# platform_smd2_driver.net
KiCad netlist of a schematic drawn in EAGLE
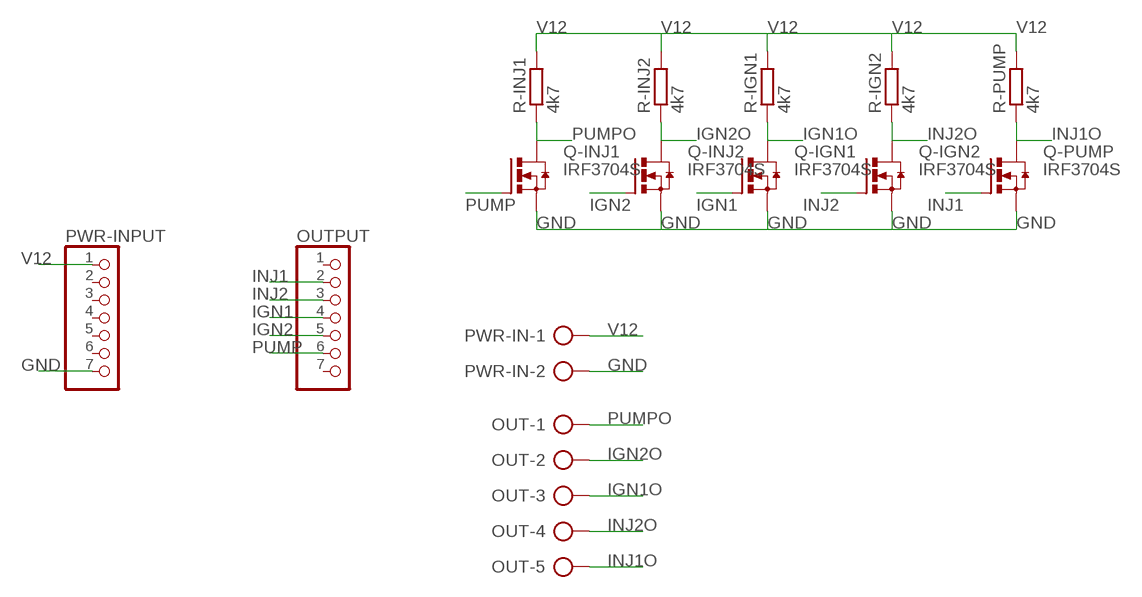
[diagram p0: schematic, sheet 1]

(export (version "E")
  (design (tool "Eeschema 10.0.6"))
  (components
    (comp (ref "OUT")
      (value "AK300/5")
      (footprint "eagle-import:AK300_5")
      (libsource (lib "eagle-import") (part "AK300/5"))
    )
    (comp (ref "OUTPUT")
      (value "PINHD-1X7")
      (footprint "eagle-import:1X07")
      (libsource (lib "eagle-import") (part "PINHD-1X7"))
    )
    (comp (ref "PWR-IN")
      (value "AK300/2")
      (footprint "eagle-import:AK300_2")
      (libsource (lib "eagle-import") (part "AK300/2"))
    )
    (comp (ref "PWR-INPUT")
      (value "PINHD-1X7")
      (footprint "eagle-import:1X07")
      (libsource (lib "eagle-import") (part "PINHD-1X7"))
    )
    (comp (ref "Q-IGN1")
      (value "IRF3704S")
      (footprint "eagle-import:D2PACK")
      (libsource (lib "eagle-import") (part "IRF3704S"))
    )
    (comp (ref "Q-IGN2")
      (value "IRF3704S")
      (footprint "eagle-import:D2PACK")
      (libsource (lib "eagle-import") (part "IRF3704S"))
    )
    (comp (ref "Q-INJ1")
      (value "IRF3704S")
      (footprint "eagle-import:D2PACK")
      (libsource (lib "eagle-import") (part "IRF3704S"))
    )
    (comp (ref "Q-INJ2")
      (value "IRF3704S")
      (footprint "eagle-import:D2PACK")
      (libsource (lib "eagle-import") (part "IRF3704S"))
    )
    (comp (ref "Q-PUMP")
      (value "IRF3704S")
      (footprint "eagle-import:D2PACK")
      (libsource (lib "eagle-import") (part "IRF3704S"))
    )
    (comp (ref "R-IGN1")
      (value "4k7")
      (footprint "eagle-import:M1206")
      (libsource (lib "eagle-import") (part "R-EU_M1206"))
    )
    (comp (ref "R-IGN2")
      (value "4k7")
      (footprint "eagle-import:M1206")
      (libsource (lib "eagle-import") (part "R-EU_M1206"))
    )
    (comp (ref "R-INJ1")
      (value "4k7")
      (footprint "eagle-import:M1206")
      (libsource (lib "eagle-import") (part "R-EU_M1206"))
    )
    (comp (ref "R-INJ2")
      (value "4k7")
      (footprint "eagle-import:M1206")
      (libsource (lib "eagle-import") (part "R-EU_M1206"))
    )
    (comp (ref "R-PUMP")
      (value "4k7")
      (footprint "eagle-import:M1206")
      (libsource (lib "eagle-import") (part "R-EU_M1206"))
    )
  )
  (nets
    (net (code "1") (name "/GND") (class "Default")
      (node (ref "PWR-IN") (pin "2") (pinfunction "KL_2") (pintype "passive"))
      (node (ref "PWR-INPUT") (pin "7") (pinfunction "7_7") (pintype "passive"))
      (node (ref "Q-IGN1") (pin "3") (pinfunction "S_3") (pintype "passive"))
      (node (ref "Q-IGN2") (pin "3") (pinfunction "S_3") (pintype "passive"))
      (node (ref "Q-INJ1") (pin "3") (pinfunction "S_3") (pintype "passive"))
      (node (ref "Q-INJ2") (pin "3") (pinfunction "S_3") (pintype "passive"))
      (node (ref "Q-PUMP") (pin "3") (pinfunction "S_3") (pintype "passive"))
    )
    (net (code "2") (name "/IGN1") (class "Default")
      (node (ref "OUTPUT") (pin "4") (pinfunction "4_4") (pintype "passive"))
      (node (ref "Q-IGN1") (pin "1") (pinfunction "G_1") (pintype "passive"))
    )
    (net (code "3") (name "/IGN1O") (class "Default")
      (node (ref "OUT") (pin "3") (pinfunction "KL_3") (pintype "passive"))
      (node (ref "Q-IGN1") (pin "2") (pinfunction "D_2") (pintype "passive"))
      (node (ref "R-IGN1") (pin "1") (pinfunction "1_1") (pintype "passive"))
    )
    (net (code "4") (name "/IGN2") (class "Default")
      (node (ref "OUTPUT") (pin "5") (pinfunction "5_5") (pintype "passive"))
      (node (ref "Q-INJ2") (pin "1") (pinfunction "G_1") (pintype "passive"))
    )
    (net (code "5") (name "/IGN2O") (class "Default")
      (node (ref "OUT") (pin "2") (pinfunction "KL_2") (pintype "passive"))
      (node (ref "Q-INJ2") (pin "2") (pinfunction "D_2") (pintype "passive"))
      (node (ref "R-INJ2") (pin "1") (pinfunction "1_1") (pintype "passive"))
    )
    (net (code "6") (name "/INJ1") (class "Default")
      (node (ref "OUTPUT") (pin "2") (pinfunction "2_2") (pintype "passive"))
      (node (ref "Q-PUMP") (pin "1") (pinfunction "G_1") (pintype "passive"))
    )
    (net (code "7") (name "/INJ1O") (class "Default")
      (node (ref "OUT") (pin "5") (pinfunction "KL_5") (pintype "passive"))
      (node (ref "Q-PUMP") (pin "2") (pinfunction "D_2") (pintype "passive"))
      (node (ref "R-PUMP") (pin "1") (pinfunction "1_1") (pintype "passive"))
    )
    (net (code "8") (name "/INJ2") (class "Default")
      (node (ref "OUTPUT") (pin "3") (pinfunction "3_3") (pintype "passive"))
      (node (ref "Q-IGN2") (pin "1") (pinfunction "G_1") (pintype "passive"))
    )
    (net (code "9") (name "/INJ2O") (class "Default")
      (node (ref "OUT") (pin "4") (pinfunction "KL_4") (pintype "passive"))
      (node (ref "Q-IGN2") (pin "2") (pinfunction "D_2") (pintype "passive"))
      (node (ref "R-IGN2") (pin "1") (pinfunction "1_1") (pintype "passive"))
    )
    (net (code "10") (name "/PUMP") (class "Default")
      (node (ref "OUTPUT") (pin "6") (pinfunction "6_6") (pintype "passive"))
      (node (ref "Q-INJ1") (pin "1") (pinfunction "G_1") (pintype "passive"))
    )
    (net (code "11") (name "/PUMPO") (class "Default")
      (node (ref "OUT") (pin "1") (pinfunction "KL_1") (pintype "passive"))
      (node (ref "Q-INJ1") (pin "2") (pinfunction "D_2") (pintype "passive"))
      (node (ref "R-INJ1") (pin "1") (pinfunction "1_1") (pintype "passive"))
    )
    (net (code "12") (name "/V12") (class "Default")
      (node (ref "PWR-IN") (pin "1") (pinfunction "KL_1") (pintype "passive"))
      (node (ref "PWR-INPUT") (pin "1") (pinfunction "1_1") (pintype "passive"))
      (node (ref "R-IGN1") (pin "2") (pinfunction "2_2") (pintype "passive"))
      (node (ref "R-IGN2") (pin "2") (pinfunction "2_2") (pintype "passive"))
      (node (ref "R-INJ1") (pin "2") (pinfunction "2_2") (pintype "passive"))
      (node (ref "R-INJ2") (pin "2") (pinfunction "2_2") (pintype "passive"))
      (node (ref "R-PUMP") (pin "2") (pinfunction "2_2") (pintype "passive"))
    )
    (net (code "13") (name "unconnected-(OUTPUT-Pad1)") (class "Default")
      (node (ref "OUTPUT") (pin "1") (pinfunction "1_1") (pintype "passive"))
    )
    (net (code "14") (name "unconnected-(OUTPUT-Pad7)") (class "Default")
      (node (ref "OUTPUT") (pin "7") (pinfunction "7_7") (pintype "passive"))
    )
    (net (code "15") (name "unconnected-(PWR-INPUT-Pad2)") (class "Default")
      (node (ref "PWR-INPUT") (pin "2") (pinfunction "2_2") (pintype "passive"))
    )
    (net (code "16") (name "unconnected-(PWR-INPUT-Pad3)") (class "Default")
      (node (ref "PWR-INPUT") (pin "3") (pinfunction "3_3") (pintype "passive"))
    )
    (net (code "17") (name "unconnected-(PWR-INPUT-Pad4)") (class "Default")
      (node (ref "PWR-INPUT") (pin "4") (pinfunction "4_4") (pintype "passive"))
    )
    (net (code "18") (name "unconnected-(PWR-INPUT-Pad5)") (class "Default")
      (node (ref "PWR-INPUT") (pin "5") (pinfunction "5_5") (pintype "passive"))
    )
    (net (code "19") (name "unconnected-(PWR-INPUT-Pad6)") (class "Default")
      (node (ref "PWR-INPUT") (pin "6") (pinfunction "6_6") (pintype "passive"))
    )
  )
)
